# x-IMU3-SA-Sync.net
KiCad netlist of a schematic drawn in Altium Designer
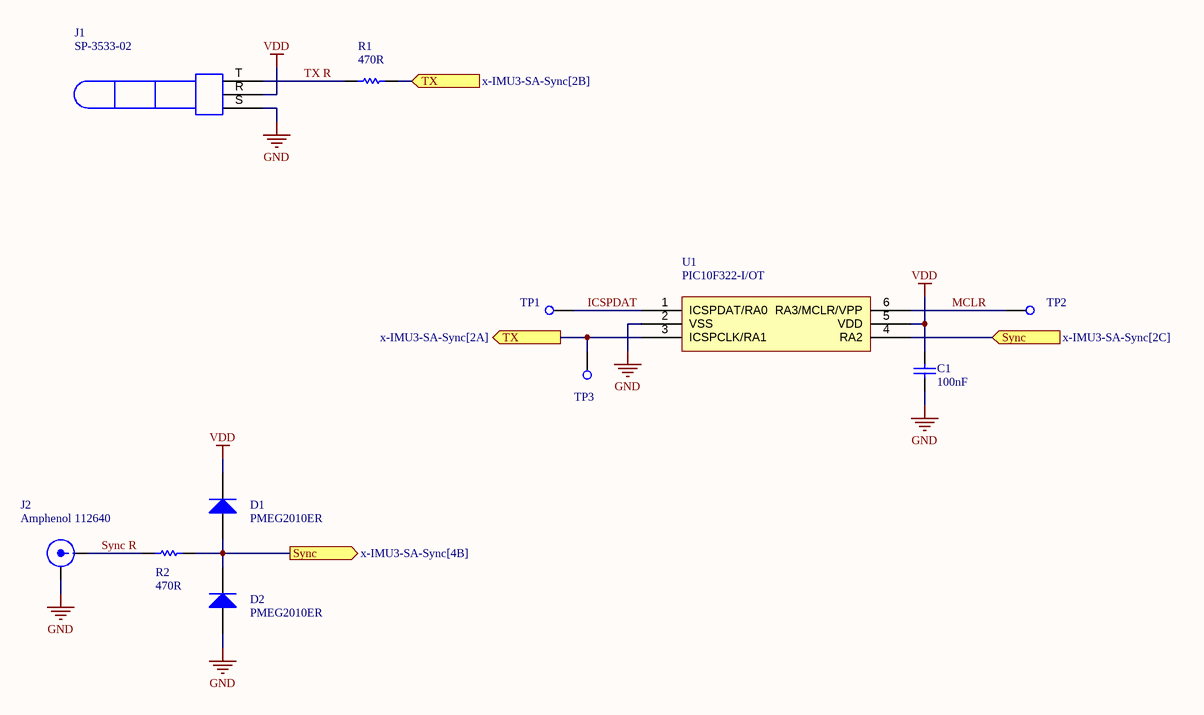
[diagram p0: x-IMU3-SA-Sync.SchDoc]

(export (version "E")
  (design (tool "Eeschema 10.0.6"))
  (components
    (comp (ref "C1") (value "100nF") (footprint "Capacitor 0402") (libsource (lib "x-io") (part "Capacitor")))
    (comp (ref "D1") (value "PMEG2010ER") (footprint "SOD-123") (libsource (lib "x-io") (part "Diode")))
    (comp (ref "D2") (value "PMEG2010ER") (footprint "SOD-123") (libsource (lib "x-io") (part "Diode")))
    (comp (ref "J1")
      (value "SP-3533-02")
      (footprint "SP-3533-02")
      (libsource (lib "x-io") (part "SP-3533-02"))
    )
    (comp (ref "J2")
      (value "Amphenol 112640")
      (footprint "Amphenol 112640")
      (libsource (lib "x-io") (part "BNC"))
    )
    (comp (ref "R1") (value "470R") (footprint "Resistor 0402") (libsource (lib "x-io") (part "Resistor")))
    (comp (ref "R2") (value "470R") (footprint "Resistor 0402") (libsource (lib "x-io") (part "Resistor")))
    (comp (ref "TP1")
      (value "Test Point")
      (footprint "Test Point 1mm")
      (libsource (lib "x-io") (part "Test Point"))
    )
    (comp (ref "TP2")
      (value "Test Point")
      (footprint "Test Point 1mm")
      (libsource (lib "x-io") (part "Test Point"))
    )
    (comp (ref "TP3")
      (value "Test Point")
      (footprint "Test Point 1mm")
      (libsource (lib "x-io") (part "Test Point"))
    )
    (comp (ref "U1")
      (value "PIC10F322-I/OT")
      (footprint "SOT-23-6")
      (libsource (lib "x-io") (part "PIC10F322-I/OT"))
    )
  )
  (nets
    (net (code "1") (name "/ICSPDAT") (class "Default")
      (node (ref "TP1") (pin "1") (pinfunction "1_1") (pintype "passive"))
      (node (ref "U1") (pin "1") (pinfunction "ICSPDAT/RA0_1") (pintype "passive"))
    )
    (net (code "2") (name "/MCLR") (class "Default")
      (node (ref "TP2") (pin "1") (pinfunction "1_1") (pintype "passive"))
      (node (ref "U1") (pin "6") (pinfunction "RA3/MCLR/VPP_6") (pintype "passive"))
    )
    (net (code "3") (name "/Sync") (class "Default")
      (node (ref "D1") (pin "A") (pinfunction "A_A") (pintype "passive"))
      (node (ref "D2") (pin "K") (pinfunction "K_K") (pintype "passive"))
      (node (ref "R2") (pin "2") (pinfunction "2_2") (pintype "passive"))
      (node (ref "U1") (pin "4") (pinfunction "RA2_4") (pintype "passive"))
    )
    (net (code "4") (name "/Sync R") (class "Default")
      (node (ref "J2") (pin "Signal") (pinfunction "Signal_Signal") (pintype "passive"))
      (node (ref "R2") (pin "1") (pinfunction "1_1") (pintype "passive"))
    )
    (net (code "5") (name "/TX") (class "Default")
      (node (ref "R1") (pin "2") (pinfunction "2_2") (pintype "passive"))
      (node (ref "TP3") (pin "1") (pinfunction "1_1") (pintype "passive"))
      (node (ref "U1") (pin "3") (pinfunction "ICSPCLK/RA1_3") (pintype "passive"))
    )
    (net (code "6") (name "/TX R") (class "Default")
      (node (ref "J1") (pin "T") (pinfunction "T_T") (pintype "passive"))
      (node (ref "R1") (pin "1") (pinfunction "1_1") (pintype "passive"))
    )
    (net (code "7") (name "GND") (class "Default")
      (node (ref "C1") (pin "1") (pinfunction "1_1") (pintype "passive"))
      (node (ref "D2") (pin "A") (pinfunction "A_A") (pintype "passive"))
      (node (ref "J1") (pin "S") (pinfunction "S_S") (pintype "passive"))
      (node (ref "J2") (pin "Shield") (pinfunction "Shield_Shield") (pintype "passive"))
      (node (ref "U1") (pin "2") (pinfunction "VSS_2") (pintype "passive"))
    )
    (net (code "8") (name "VDD") (class "Default")
      (node (ref "C1") (pin "2") (pinfunction "2_2") (pintype "passive"))
      (node (ref "D1") (pin "K") (pinfunction "K_K") (pintype "passive"))
      (node (ref "J1") (pin "R") (pinfunction "R_R") (pintype "passive"))
      (node (ref "U1") (pin "5") (pinfunction "VDD_5") (pintype "passive"))
    )
  )
)
